# MCU.net
KiCad netlist of a schematic drawn in Altium Designer
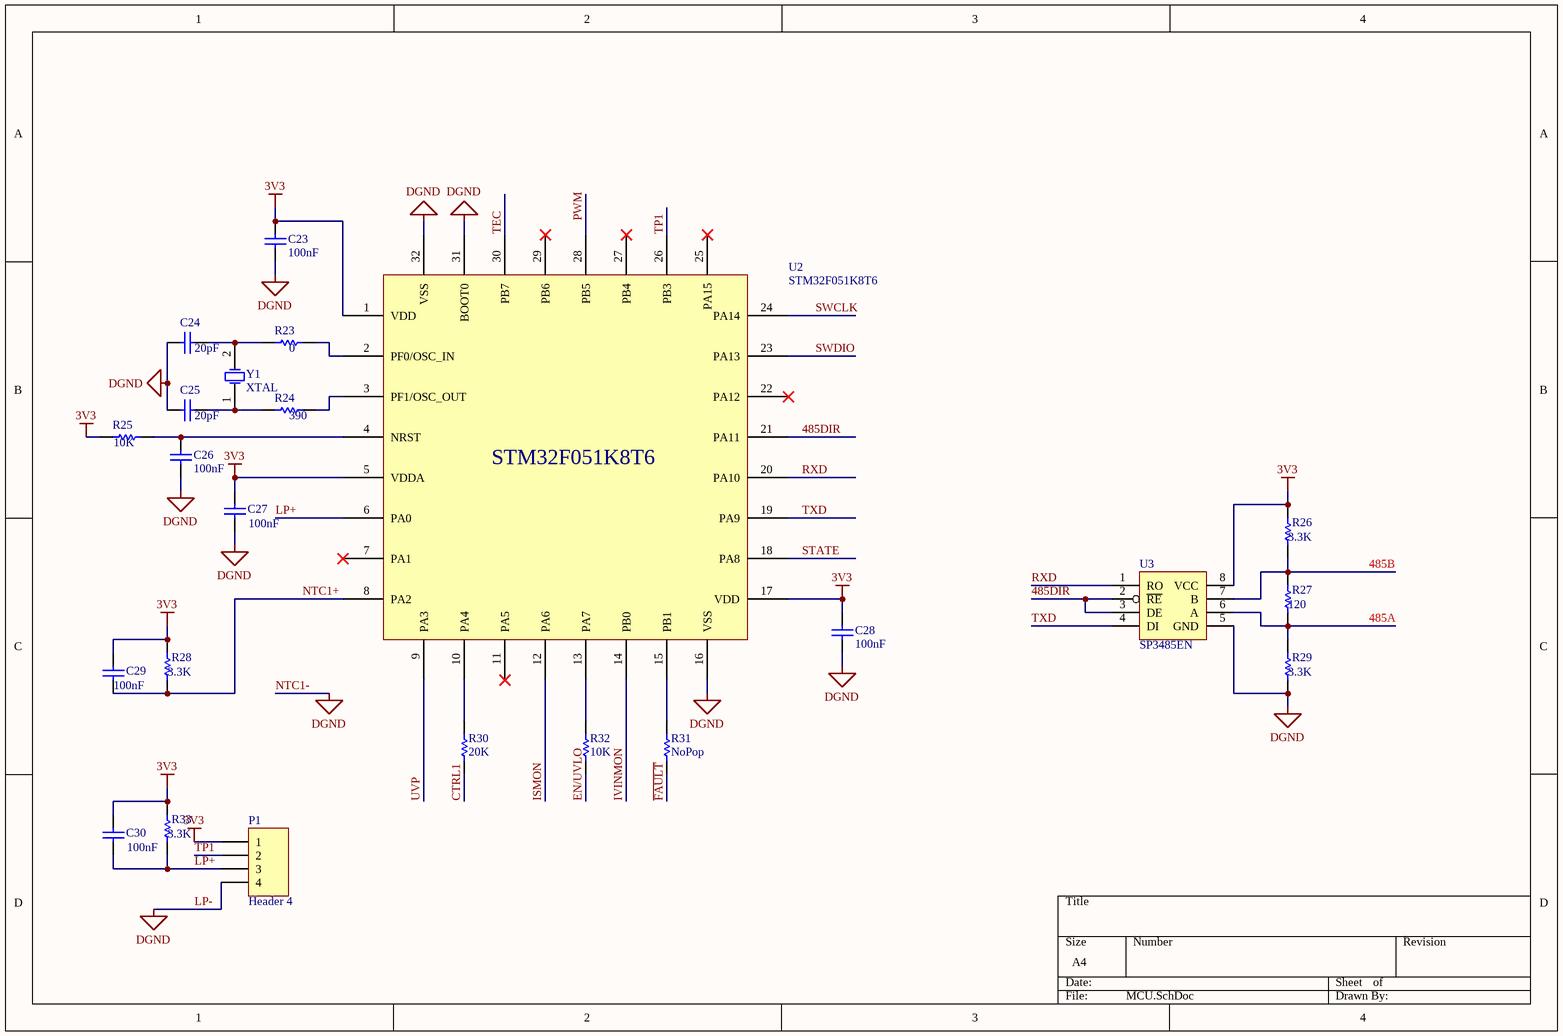
[diagram p0: MCU.SchDoc]

(export (version "E")
  (design (tool "Eeschema 10.0.6"))
  (components
    (comp (ref "C23")
      (value "100nF")
      (footprint "1608[0603]")
      (description "Capacitor")
      (fields (field (name "PUBLISHER") "Altium Limited"))
      (libsource (lib "Miscellaneous Devices") (part "Cap"))
    )
    (comp (ref "C24")
      (value "20pF")
      (footprint "1608[0603]")
      (description "Capacitor")
      (fields (field (name "PUBLISHER") "Altium Limited"))
      (libsource (lib "Miscellaneous Devices") (part "Cap"))
    )
    (comp (ref "C25")
      (value "20pF")
      (footprint "1608[0603]")
      (description "Capacitor")
      (fields (field (name "PUBLISHER") "Altium Limited"))
      (libsource (lib "Miscellaneous Devices") (part "Cap"))
    )
    (comp (ref "C26")
      (value "100nF")
      (footprint "1608[0603]")
      (description "Capacitor")
      (fields (field (name "PUBLISHER") "Altium Limited"))
      (libsource (lib "Miscellaneous Devices") (part "Cap"))
    )
    (comp (ref "C27")
      (value "100nF")
      (footprint "1608[0603]")
      (description "Capacitor")
      (fields (field (name "PUBLISHER") "Altium Limited"))
      (libsource (lib "Miscellaneous Devices") (part "Cap"))
    )
    (comp (ref "C28")
      (value "100nF")
      (footprint "1608[0603]")
      (description "Capacitor")
      (fields (field (name "PUBLISHER") "Altium Limited"))
      (libsource (lib "Miscellaneous Devices") (part "Cap"))
    )
    (comp (ref "C29")
      (value "100nF")
      (footprint "1608[0603]")
      (description "Capacitor")
      (fields (field (name "PUBLISHER") "Altium Limited"))
      (libsource (lib "Miscellaneous Devices") (part "Cap"))
    )
    (comp (ref "C30")
      (value "100nF")
      (footprint "1608[0603]")
      (description "Capacitor")
      (fields (field (name "PUBLISHER") "Altium Limited"))
      (libsource (lib "Miscellaneous Devices") (part "Cap"))
    )
    (comp (ref "P1")
      (value "Header 4")
      (footprint "HDR1X4")
      (description "Header, 4-Pin")
      (fields (field (name "PUBLISHER") "Altium Limited"))
      (libsource (lib "Miscellaneous Connectors") (part "Header 4"))
    )
    (comp (ref "R23")
      (value "0")
      (footprint "1608[0603]")
      (description "Resistor")
      (fields (field (name "PUBLISHER") "Altium Limited"))
      (libsource (lib "Miscellaneous Devices") (part "Res1"))
    )
    (comp (ref "R24")
      (value "390")
      (footprint "1608[0603]")
      (description "Resistor")
      (fields (field (name "PUBLISHER") "Altium Limited"))
      (libsource (lib "Miscellaneous Devices") (part "Res1"))
    )
    (comp (ref "R25")
      (value "10K")
      (footprint "1608[0603]")
      (description "Resistor")
      (fields (field (name "PUBLISHER") "Altium Limited"))
      (libsource (lib "Miscellaneous Devices") (part "Res1"))
    )
    (comp (ref "R26")
      (value "3.3K")
      (footprint "1608[0603]")
      (description "Resistor")
      (fields (field (name "PUBLISHER") "Altium Limited"))
      (libsource (lib "Miscellaneous Devices") (part "Res1"))
    )
    (comp (ref "R27")
      (value "120")
      (footprint "1608[0603]")
      (description "Resistor")
      (fields (field (name "PUBLISHER") "Altium Limited"))
      (libsource (lib "Miscellaneous Devices") (part "Res1"))
    )
    (comp (ref "R28")
      (value "3.3K")
      (footprint "1608[0603]")
      (description "Resistor")
      (fields (field (name "PUBLISHER") "Altium Limited"))
      (libsource (lib "Miscellaneous Devices") (part "Res1"))
    )
    (comp (ref "R29")
      (value "3.3K")
      (footprint "1608[0603]")
      (description "Resistor")
      (fields (field (name "PUBLISHER") "Altium Limited"))
      (libsource (lib "Miscellaneous Devices") (part "Res1"))
    )
    (comp (ref "R30")
      (value "20K")
      (footprint "1608[0603]")
      (description "Resistor")
      (fields (field (name "PUBLISHER") "Altium Limited"))
      (libsource (lib "Miscellaneous Devices") (part "Res1"))
    )
    (comp (ref "R31")
      (value "NoPop")
      (footprint "1608[0603]")
      (description "Resistor")
      (fields (field (name "PUBLISHER") "Altium Limited"))
      (libsource (lib "Miscellaneous Devices") (part "Res1"))
    )
    (comp (ref "R32")
      (value "10K")
      (footprint "1608[0603]")
      (description "Resistor")
      (fields (field (name "PUBLISHER") "Altium Limited"))
      (libsource (lib "Miscellaneous Devices") (part "Res1"))
    )
    (comp (ref "R33")
      (value "3.3K")
      (footprint "1608[0603]")
      (description "Resistor")
      (fields (field (name "PUBLISHER") "Altium Limited"))
      (libsource (lib "Miscellaneous Devices") (part "Res1"))
    )
    (comp (ref "U2")
      (value "STM32F051K8T6")
      (footprint "TQFP80P900X900X160-32N")
      (libsource (lib "Laser-LiuXin") (part "MCU_STM32F051K8T6"))
    )
    (comp (ref "U3")
      (value "SP3485EN")
      (footprint "Laser-LiuXin:SOIC127P600-8N")
      (description "Low-Power, Slew-Rate-Limited  RS-485/RS-422 Transceivers")
      (libsource (lib "Laser-LiuXin") (part "LGC_RS485"))
    )
    (comp (ref "Y1")
      (value "XTAL")
      (footprint "Laser-LiuXin:XTAL_SMT")
      (description "Crystal Oscillator")
      (fields (field (name "PUBLISHER") "Altium Limited"))
      (libsource (lib "Miscellaneous Devices") (part "XTAL"))
    )
  )
  (nets
    (net (code "1") (name "/485A") (class "Default")
      (node (ref "R27") (pin "1") (pinfunction "1_1") (pintype "passive"))
      (node (ref "R29") (pin "2") (pinfunction "2_2") (pintype "passive"))
      (node (ref "U3") (pin "6") (pinfunction "A_6") (pintype "passive"))
    )
    (net (code "2") (name "/485B") (class "Default")
      (node (ref "R26") (pin "1") (pinfunction "1_1") (pintype "passive"))
      (node (ref "R27") (pin "2") (pinfunction "2_2") (pintype "passive"))
      (node (ref "U3") (pin "7") (pinfunction "B_7") (pintype "passive"))
    )
    (net (code "3") (name "/485DIR") (class "Default")
      (node (ref "U2") (pin "21") (pinfunction "PA11_21") (pintype "passive"))
      (node (ref "U3") (pin "2") (pinfunction "~{RE}_2") (pintype "passive"))
      (node (ref "U3") (pin "3") (pinfunction "DE_3") (pintype "passive"))
    )
    (net (code "5") (name "/CTRL1") (class "Default")
      (node (ref "R30") (pin "1") (pinfunction "1_1") (pintype "passive"))
    )
    (net (code "6") (name "/EN{slash}UVLO") (class "Default")
      (node (ref "R32") (pin "1") (pinfunction "1_1") (pintype "passive"))
    )
    (net (code "7") (name "/ISMON") (class "Default")
      (node (ref "U2") (pin "12") (pinfunction "PA6_12") (pintype "passive"))
    )
    (net (code "8") (name "/IVINMON") (class "Default")
      (node (ref "U2") (pin "14") (pinfunction "PB0_14") (pintype "passive"))
    )
    (net (code "9") (name "/LP+") (class "Default")
      (node (ref "C30") (pin "2") (pinfunction "2_2") (pintype "passive"))
      (node (ref "P1") (pin "3") (pinfunction "3_3") (pintype "passive"))
      (node (ref "R33") (pin "2") (pinfunction "2_2") (pintype "passive"))
      (node (ref "U2") (pin "6") (pinfunction "PA0_6") (pintype "passive"))
    )
    (net (code "10") (name "/NTC1+") (class "Default")
      (node (ref "C29") (pin "2") (pinfunction "2_2") (pintype "passive"))
      (node (ref "R28") (pin "2") (pinfunction "2_2") (pintype "passive"))
      (node (ref "U2") (pin "8") (pinfunction "PA2_8") (pintype "passive"))
    )
    (net (code "11") (name "/PWM") (class "Default")
      (node (ref "U2") (pin "28") (pinfunction "PB5_28") (pintype "passive"))
    )
    (net (code "12") (name "/RXD") (class "Default")
      (node (ref "U2") (pin "20") (pinfunction "PA10_20") (pintype "passive"))
      (node (ref "U3") (pin "1") (pinfunction "RO_1") (pintype "passive"))
    )
    (net (code "13") (name "/STATE") (class "Default")
      (node (ref "U2") (pin "18") (pinfunction "PA8_18") (pintype "passive"))
    )
    (net (code "14") (name "/SWCLK") (class "Default")
      (node (ref "U2") (pin "24") (pinfunction "PA14_24") (pintype "passive"))
    )
    (net (code "15") (name "/SWDIO") (class "Default")
      (node (ref "U2") (pin "23") (pinfunction "PA13_23") (pintype "passive"))
    )
    (net (code "16") (name "/TEC") (class "Default")
      (node (ref "U2") (pin "30") (pinfunction "PB7_30") (pintype "passive"))
    )
    (net (code "17") (name "/TP1") (class "Default")
      (node (ref "P1") (pin "2") (pinfunction "2_2") (pintype "passive"))
      (node (ref "U2") (pin "26") (pinfunction "PB3_26") (pintype "passive"))
    )
    (net (code "18") (name "/TXD") (class "Default")
      (node (ref "U2") (pin "19") (pinfunction "PA9_19") (pintype "passive"))
      (node (ref "U3") (pin "4") (pinfunction "DI_4") (pintype "passive"))
    )
    (net (code "19") (name "/UVP") (class "Default")
      (node (ref "U2") (pin "9") (pinfunction "PA3_9") (pintype "passive"))
    )
    (net (code "20") (name "/~{FAULT}") (class "Default")
      (node (ref "R31") (pin "1") (pinfunction "1_1") (pintype "passive"))
    )
    (net (code "21") (name "3V3") (class "Default")
      (node (ref "C23") (pin "2") (pinfunction "2_2") (pintype "passive"))
      (node (ref "C27") (pin "1") (pinfunction "1_1") (pintype "passive"))
      (node (ref "C28") (pin "2") (pinfunction "2_2") (pintype "passive"))
      (node (ref "C29") (pin "1") (pinfunction "1_1") (pintype "passive"))
      (node (ref "C30") (pin "1") (pinfunction "1_1") (pintype "passive"))
      (node (ref "P1") (pin "1") (pinfunction "1_1") (pintype "passive"))
      (node (ref "R25") (pin "2") (pinfunction "2_2") (pintype "passive"))
      (node (ref "R26") (pin "2") (pinfunction "2_2") (pintype "passive"))
      (node (ref "R28") (pin "1") (pinfunction "1_1") (pintype "passive"))
      (node (ref "R33") (pin "1") (pinfunction "1_1") (pintype "passive"))
      (node (ref "U2") (pin "1") (pinfunction "VDD_1") (pintype "passive"))
      (node (ref "U2") (pin "17") (pinfunction "VDD_17") (pintype "passive"))
      (node (ref "U2") (pin "5") (pinfunction "VDDA_5") (pintype "passive"))
      (node (ref "U3") (pin "8") (pinfunction "VCC_8") (pintype "passive"))
    )
    (net (code "22") (name "DGND") (class "Default")
      (node (ref "C23") (pin "1") (pinfunction "1_1") (pintype "passive"))
      (node (ref "C24") (pin "2") (pinfunction "2_2") (pintype "passive"))
      (node (ref "C25") (pin "2") (pinfunction "2_2") (pintype "passive"))
      (node (ref "C26") (pin "1") (pinfunction "1_1") (pintype "passive"))
      (node (ref "C27") (pin "2") (pinfunction "2_2") (pintype "passive"))
      (node (ref "C28") (pin "1") (pinfunction "1_1") (pintype "passive"))
      (node (ref "P1") (pin "4") (pinfunction "4_4") (pintype "passive"))
      (node (ref "R29") (pin "1") (pinfunction "1_1") (pintype "passive"))
      (node (ref "U2") (pin "16") (pinfunction "VSS_16") (pintype "passive"))
      (node (ref "U2") (pin "31") (pinfunction "BOOT0_31") (pintype "passive"))
      (node (ref "U2") (pin "32") (pinfunction "VSS_32") (pintype "passive"))
      (node (ref "U3") (pin "5") (pinfunction "GND_5") (pintype "passive"))
    )
    (net (code "23") (name "Net-(U2-NRST)") (class "Default")
      (node (ref "C26") (pin "2") (pinfunction "2_2") (pintype "passive"))
      (node (ref "R25") (pin "1") (pinfunction "1_1") (pintype "passive"))
      (node (ref "U2") (pin "4") (pinfunction "NRST_4") (pintype "passive"))
    )
    (net (code "24") (name "Net-(U2-PA4)") (class "Default")
      (node (ref "R30") (pin "2") (pinfunction "2_2") (pintype "passive"))
      (node (ref "U2") (pin "10") (pinfunction "PA4_10") (pintype "passive"))
    )
    (net (code "25") (name "Net-(U2-PA7)") (class "Default")
      (node (ref "R32") (pin "2") (pinfunction "2_2") (pintype "passive"))
      (node (ref "U2") (pin "13") (pinfunction "PA7_13") (pintype "passive"))
    )
    (net (code "26") (name "Net-(U2-PB1)") (class "Default")
      (node (ref "R31") (pin "2") (pinfunction "2_2") (pintype "passive"))
      (node (ref "U2") (pin "15") (pinfunction "PB1_15") (pintype "passive"))
    )
    (net (code "27") (name "Net-(U2-PF0{slash}OSC_IN)") (class "Default")
      (node (ref "R23") (pin "2") (pinfunction "2_2") (pintype "passive"))
      (node (ref "U2") (pin "2") (pinfunction "PF0/OSC_IN_2") (pintype "passive"))
    )
    (net (code "28") (name "Net-(U2-PF1{slash}OSC_OUT)") (class "Default")
      (node (ref "R24") (pin "2") (pinfunction "2_2") (pintype "passive"))
      (node (ref "U2") (pin "3") (pinfunction "PF1/OSC_OUT_3") (pintype "passive"))
    )
    (net (code "29") (name "Net-(Y1-OSC1)") (class "Default")
      (node (ref "C25") (pin "1") (pinfunction "1_1") (pintype "passive"))
      (node (ref "R24") (pin "1") (pinfunction "1_1") (pintype "passive"))
      (node (ref "Y1") (pin "1") (pinfunction "OSC1_1") (pintype "passive"))
    )
    (net (code "30") (name "Net-(Y1-OSC2)") (class "Default")
      (node (ref "C24") (pin "1") (pinfunction "1_1") (pintype "passive"))
      (node (ref "R23") (pin "1") (pinfunction "1_1") (pintype "passive"))
      (node (ref "Y1") (pin "2") (pinfunction "OSC2_2") (pintype "passive"))
    )
    (net (code "31") (name "unconnected-(U2-PA1-Pad7)") (class "Default")
      (node (ref "U2") (pin "7") (pinfunction "PA1_7") (pintype "passive+no_connect"))
    )
    (net (code "32") (name "unconnected-(U2-PA5-Pad11)") (class "Default")
      (node (ref "U2") (pin "11") (pinfunction "PA5_11") (pintype "passive+no_connect"))
    )
    (net (code "33") (name "unconnected-(U2-PA12-Pad22)") (class "Default")
      (node (ref "U2") (pin "22") (pinfunction "PA12_22") (pintype "passive+no_connect"))
    )
    (net (code "34") (name "unconnected-(U2-PA15-Pad25)") (class "Default")
      (node (ref "U2") (pin "25") (pinfunction "PA15_25") (pintype "passive+no_connect"))
    )
    (net (code "35") (name "unconnected-(U2-PB4-Pad27)") (class "Default")
      (node (ref "U2") (pin "27") (pinfunction "PB4_27") (pintype "passive+no_connect"))
    )
    (net (code "36") (name "unconnected-(U2-PB6-Pad29)") (class "Default")
      (node (ref "U2") (pin "29") (pinfunction "PB6_29") (pintype "passive+no_connect"))
    )
  )
)
